# NixiTubeClock_IN-14.net
KiCad netlist of a schematic drawn in EAGLE
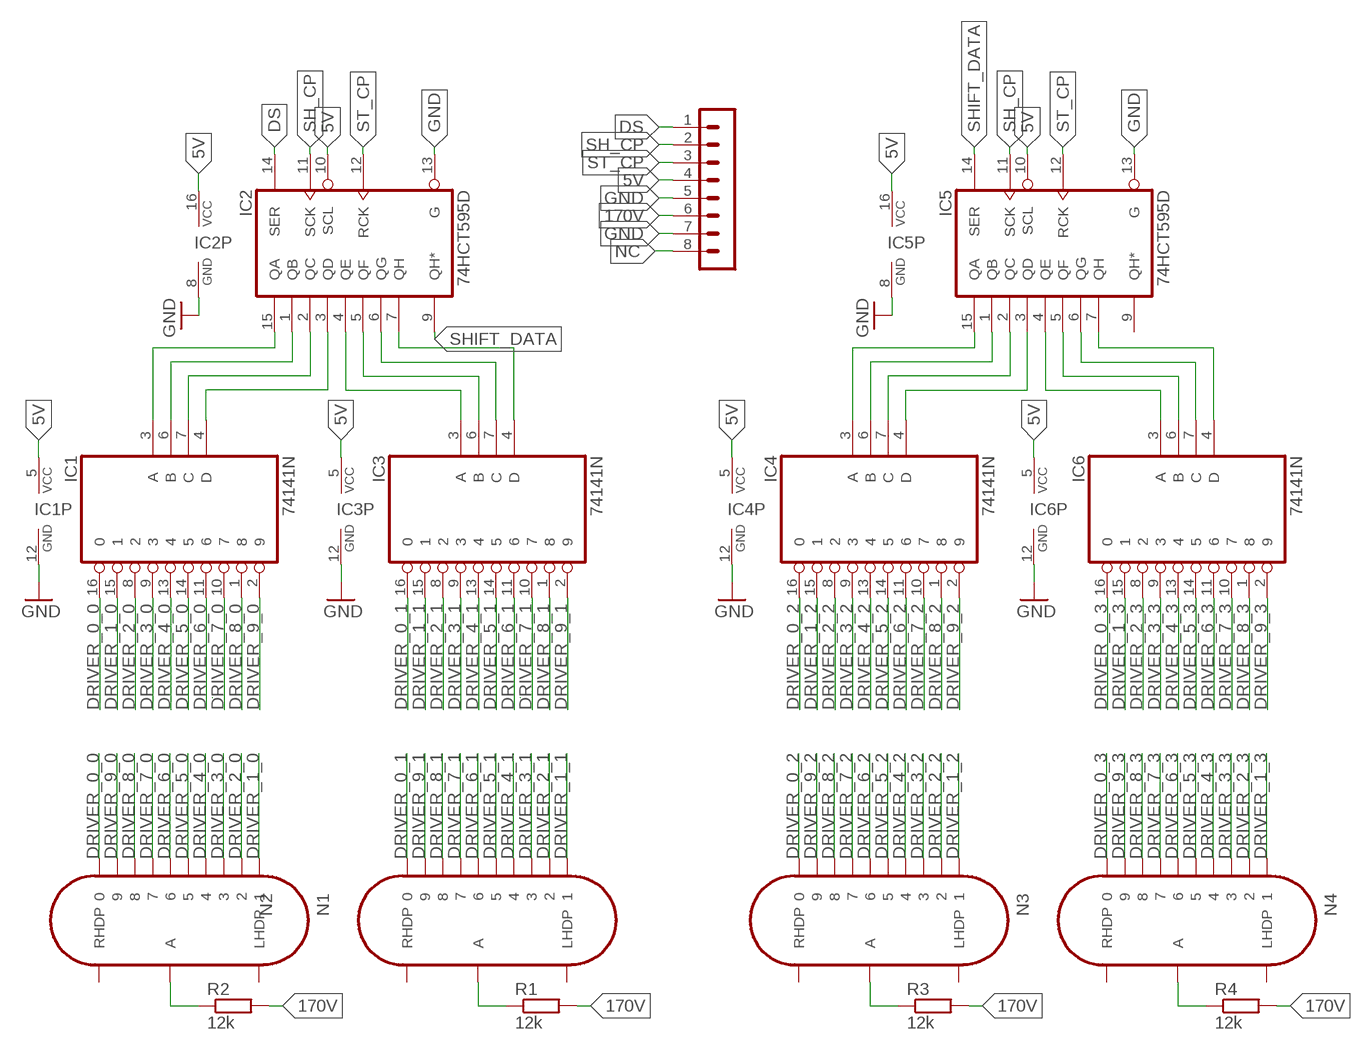
[diagram p0: schematic, sheet 1]

(export (version "E")
  (design (tool "Eeschema 10.0.6"))
  (components
    (comp (ref "IC1")
      (value "74141N")
      (footprint "eagle-import:DIL16")
      (libsource (lib "eagle-import") (part "74141N"))
    )
    (comp (ref "IC2")
      (value "74HCT595D")
      (footprint "eagle-import:SO16")
      (libsource (lib "eagle-import") (part "74595DHCT"))
    )
    (comp (ref "IC3")
      (value "74141N")
      (footprint "eagle-import:DIL16")
      (libsource (lib "eagle-import") (part "74141N"))
    )
    (comp (ref "IC4")
      (value "74141N")
      (footprint "eagle-import:DIL16")
      (libsource (lib "eagle-import") (part "74141N"))
    )
    (comp (ref "IC5")
      (value "74HCT595D")
      (footprint "eagle-import:SO16")
      (libsource (lib "eagle-import") (part "74595DHCT"))
    )
    (comp (ref "IC6")
      (value "74141N")
      (footprint "eagle-import:DIL16")
      (libsource (lib "eagle-import") (part "74141N"))
    )
    (comp (ref "N1")
      (value "IN-14")
      (footprint "eagle-import:IN-14")
      (libsource (lib "eagle-import") (part "IN-14"))
    )
    (comp (ref "N2")
      (value "IN-14")
      (footprint "eagle-import:IN-14")
      (libsource (lib "eagle-import") (part "IN-14"))
    )
    (comp (ref "N3")
      (value "IN-14")
      (footprint "eagle-import:IN-14")
      (libsource (lib "eagle-import") (part "IN-14"))
    )
    (comp (ref "N4")
      (value "IN-14")
      (footprint "eagle-import:IN-14")
      (libsource (lib "eagle-import") (part "IN-14"))
    )
    (comp (ref "R1")
      (value "12k")
      (footprint "eagle-import:R1206")
      (libsource (lib "eagle-import") (part "R-EU_1206R1206"))
    )
    (comp (ref "R2")
      (value "12k")
      (footprint "eagle-import:R1206")
      (libsource (lib "eagle-import") (part "R-EU_1206R1206"))
    )
    (comp (ref "R3")
      (value "12k")
      (footprint "eagle-import:R1206")
      (libsource (lib "eagle-import") (part "R-EU_1206R1206"))
    )
    (comp (ref "R4")
      (value "12k")
      (footprint "eagle-import:R1206")
      (libsource (lib "eagle-import") (part "R-EU_1206R1206"))
    )
    (comp (ref "SV2")
      (value "PINHEADER-1X8")
      (footprint "eagle-import:MA08-1")
      (libsource (lib "eagle-import") (part "PINHEADER-1X8"))
    )
  )
  (nets
    (net (code "1") (name "/DRIVER_0_0") (class "Default")
      (node (ref "IC1") (pin "16") (pinfunction "0_16") (pintype "open_collector"))
      (node (ref "N1") (pin "0") (pinfunction "0_0") (pintype "bidirectional"))
    )
    (net (code "2") (name "/DRIVER_0_1") (class "Default")
      (node (ref "IC3") (pin "16") (pinfunction "0_16") (pintype "open_collector"))
      (node (ref "N2") (pin "0") (pinfunction "0_0") (pintype "bidirectional"))
    )
    (net (code "3") (name "/DRIVER_0_2") (class "Default")
      (node (ref "IC4") (pin "16") (pinfunction "0_16") (pintype "open_collector"))
      (node (ref "N3") (pin "0") (pinfunction "0_0") (pintype "bidirectional"))
    )
    (net (code "4") (name "/DRIVER_0_3") (class "Default")
      (node (ref "IC6") (pin "16") (pinfunction "0_16") (pintype "open_collector"))
      (node (ref "N4") (pin "0") (pinfunction "0_0") (pintype "bidirectional"))
    )
    (net (code "5") (name "/DRIVER_1_0") (class "Default")
      (node (ref "IC1") (pin "15") (pinfunction "1_15") (pintype "open_collector"))
      (node (ref "N1") (pin "1") (pinfunction "1_1") (pintype "bidirectional"))
    )
    (net (code "6") (name "/DRIVER_1_1") (class "Default")
      (node (ref "IC3") (pin "15") (pinfunction "1_15") (pintype "open_collector"))
      (node (ref "N2") (pin "1") (pinfunction "1_1") (pintype "bidirectional"))
    )
    (net (code "7") (name "/DRIVER_1_2") (class "Default")
      (node (ref "IC4") (pin "15") (pinfunction "1_15") (pintype "open_collector"))
      (node (ref "N3") (pin "1") (pinfunction "1_1") (pintype "bidirectional"))
    )
    (net (code "8") (name "/DRIVER_1_3") (class "Default")
      (node (ref "IC6") (pin "15") (pinfunction "1_15") (pintype "open_collector"))
      (node (ref "N4") (pin "1") (pinfunction "1_1") (pintype "bidirectional"))
    )
    (net (code "9") (name "/DRIVER_2_0") (class "Default")
      (node (ref "IC1") (pin "8") (pinfunction "2_8") (pintype "open_collector"))
      (node (ref "N1") (pin "2") (pinfunction "2_2") (pintype "bidirectional"))
    )
    (net (code "10") (name "/DRIVER_2_1") (class "Default")
      (node (ref "IC3") (pin "8") (pinfunction "2_8") (pintype "open_collector"))
      (node (ref "N2") (pin "2") (pinfunction "2_2") (pintype "bidirectional"))
    )
    (net (code "11") (name "/DRIVER_2_2") (class "Default")
      (node (ref "IC4") (pin "8") (pinfunction "2_8") (pintype "open_collector"))
      (node (ref "N3") (pin "2") (pinfunction "2_2") (pintype "bidirectional"))
    )
    (net (code "12") (name "/DRIVER_2_3") (class "Default")
      (node (ref "IC6") (pin "8") (pinfunction "2_8") (pintype "open_collector"))
      (node (ref "N4") (pin "2") (pinfunction "2_2") (pintype "bidirectional"))
    )
    (net (code "13") (name "/DRIVER_3_0") (class "Default")
      (node (ref "IC1") (pin "9") (pinfunction "3_9") (pintype "open_collector"))
      (node (ref "N1") (pin "3") (pinfunction "3_3") (pintype "bidirectional"))
    )
    (net (code "14") (name "/DRIVER_3_1") (class "Default")
      (node (ref "IC3") (pin "9") (pinfunction "3_9") (pintype "open_collector"))
      (node (ref "N2") (pin "3") (pinfunction "3_3") (pintype "bidirectional"))
    )
    (net (code "15") (name "/DRIVER_3_2") (class "Default")
      (node (ref "IC4") (pin "9") (pinfunction "3_9") (pintype "open_collector"))
      (node (ref "N3") (pin "3") (pinfunction "3_3") (pintype "bidirectional"))
    )
    (net (code "16") (name "/DRIVER_3_3") (class "Default")
      (node (ref "IC6") (pin "9") (pinfunction "3_9") (pintype "open_collector"))
      (node (ref "N4") (pin "3") (pinfunction "3_3") (pintype "bidirectional"))
    )
    (net (code "17") (name "/DRIVER_4_0") (class "Default")
      (node (ref "IC1") (pin "13") (pinfunction "4_13") (pintype "open_collector"))
      (node (ref "N1") (pin "4") (pinfunction "4_4") (pintype "bidirectional"))
    )
    (net (code "18") (name "/DRIVER_4_1") (class "Default")
      (node (ref "IC3") (pin "13") (pinfunction "4_13") (pintype "open_collector"))
      (node (ref "N2") (pin "4") (pinfunction "4_4") (pintype "bidirectional"))
    )
    (net (code "19") (name "/DRIVER_4_2") (class "Default")
      (node (ref "IC4") (pin "13") (pinfunction "4_13") (pintype "open_collector"))
      (node (ref "N3") (pin "4") (pinfunction "4_4") (pintype "bidirectional"))
    )
    (net (code "20") (name "/DRIVER_4_3") (class "Default")
      (node (ref "IC6") (pin "13") (pinfunction "4_13") (pintype "open_collector"))
      (node (ref "N4") (pin "4") (pinfunction "4_4") (pintype "bidirectional"))
    )
    (net (code "21") (name "/DRIVER_5_0") (class "Default")
      (node (ref "IC1") (pin "14") (pinfunction "5_14") (pintype "open_collector"))
      (node (ref "N1") (pin "5") (pinfunction "5_5") (pintype "bidirectional"))
    )
    (net (code "22") (name "/DRIVER_5_1") (class "Default")
      (node (ref "IC3") (pin "14") (pinfunction "5_14") (pintype "open_collector"))
      (node (ref "N2") (pin "5") (pinfunction "5_5") (pintype "bidirectional"))
    )
    (net (code "23") (name "/DRIVER_5_2") (class "Default")
      (node (ref "IC4") (pin "14") (pinfunction "5_14") (pintype "open_collector"))
      (node (ref "N3") (pin "5") (pinfunction "5_5") (pintype "bidirectional"))
    )
    (net (code "24") (name "/DRIVER_5_3") (class "Default")
      (node (ref "IC6") (pin "14") (pinfunction "5_14") (pintype "open_collector"))
      (node (ref "N4") (pin "5") (pinfunction "5_5") (pintype "bidirectional"))
    )
    (net (code "25") (name "/DRIVER_6_0") (class "Default")
      (node (ref "IC1") (pin "11") (pinfunction "6_11") (pintype "open_collector"))
      (node (ref "N1") (pin "6") (pinfunction "6_6") (pintype "bidirectional"))
    )
    (net (code "26") (name "/DRIVER_6_1") (class "Default")
      (node (ref "IC3") (pin "11") (pinfunction "6_11") (pintype "open_collector"))
      (node (ref "N2") (pin "6") (pinfunction "6_6") (pintype "bidirectional"))
    )
    (net (code "27") (name "/DRIVER_6_2") (class "Default")
      (node (ref "IC4") (pin "11") (pinfunction "6_11") (pintype "open_collector"))
      (node (ref "N3") (pin "6") (pinfunction "6_6") (pintype "bidirectional"))
    )
    (net (code "28") (name "/DRIVER_6_3") (class "Default")
      (node (ref "IC6") (pin "11") (pinfunction "6_11") (pintype "open_collector"))
      (node (ref "N4") (pin "6") (pinfunction "6_6") (pintype "bidirectional"))
    )
    (net (code "29") (name "/DRIVER_7_0") (class "Default")
      (node (ref "IC1") (pin "10") (pinfunction "7_10") (pintype "open_collector"))
      (node (ref "N1") (pin "7") (pinfunction "7_7") (pintype "bidirectional"))
    )
    (net (code "30") (name "/DRIVER_7_1") (class "Default")
      (node (ref "IC3") (pin "10") (pinfunction "7_10") (pintype "open_collector"))
      (node (ref "N2") (pin "7") (pinfunction "7_7") (pintype "bidirectional"))
    )
    (net (code "31") (name "/DRIVER_7_2") (class "Default")
      (node (ref "IC4") (pin "10") (pinfunction "7_10") (pintype "open_collector"))
      (node (ref "N3") (pin "7") (pinfunction "7_7") (pintype "bidirectional"))
    )
    (net (code "32") (name "/DRIVER_7_3") (class "Default")
      (node (ref "IC6") (pin "10") (pinfunction "7_10") (pintype "open_collector"))
      (node (ref "N4") (pin "7") (pinfunction "7_7") (pintype "bidirectional"))
    )
    (net (code "33") (name "/DRIVER_8_0") (class "Default")
      (node (ref "IC1") (pin "1") (pinfunction "8_1") (pintype "open_collector"))
      (node (ref "N1") (pin "8") (pinfunction "8_8") (pintype "bidirectional"))
    )
    (net (code "34") (name "/DRIVER_8_1") (class "Default")
      (node (ref "IC3") (pin "1") (pinfunction "8_1") (pintype "open_collector"))
      (node (ref "N2") (pin "8") (pinfunction "8_8") (pintype "bidirectional"))
    )
    (net (code "35") (name "/DRIVER_8_2") (class "Default")
      (node (ref "IC4") (pin "1") (pinfunction "8_1") (pintype "open_collector"))
      (node (ref "N3") (pin "8") (pinfunction "8_8") (pintype "bidirectional"))
    )
    (net (code "36") (name "/DRIVER_8_3") (class "Default")
      (node (ref "IC6") (pin "1") (pinfunction "8_1") (pintype "open_collector"))
      (node (ref "N4") (pin "8") (pinfunction "8_8") (pintype "bidirectional"))
    )
    (net (code "37") (name "/DRIVER_9_0") (class "Default")
      (node (ref "IC1") (pin "2") (pinfunction "9_2") (pintype "open_collector"))
      (node (ref "N1") (pin "9") (pinfunction "9_9") (pintype "bidirectional"))
    )
    (net (code "38") (name "/DRIVER_9_1") (class "Default")
      (node (ref "IC3") (pin "2") (pinfunction "9_2") (pintype "open_collector"))
      (node (ref "N2") (pin "9") (pinfunction "9_9") (pintype "bidirectional"))
    )
    (net (code "39") (name "/DRIVER_9_2") (class "Default")
      (node (ref "IC4") (pin "2") (pinfunction "9_2") (pintype "open_collector"))
      (node (ref "N3") (pin "9") (pinfunction "9_9") (pintype "bidirectional"))
    )
    (net (code "40") (name "/DRIVER_9_3") (class "Default")
      (node (ref "IC6") (pin "2") (pinfunction "9_2") (pintype "open_collector"))
      (node (ref "N4") (pin "9") (pinfunction "9_9") (pintype "bidirectional"))
    )
    (net (code "41") (name "5V") (class "Default")
      (node (ref "IC1") (pin "5") (pinfunction "VCC_5") (pintype "power_in"))
      (node (ref "IC2") (pin "10") (pinfunction "SCL_10") (pintype "input"))
      (node (ref "IC2") (pin "16") (pinfunction "VCC_16") (pintype "power_in"))
      (node (ref "IC3") (pin "5") (pinfunction "VCC_5") (pintype "power_in"))
      (node (ref "IC4") (pin "5") (pinfunction "VCC_5") (pintype "power_in"))
      (node (ref "IC5") (pin "10") (pinfunction "SCL_10") (pintype "input"))
      (node (ref "IC5") (pin "16") (pinfunction "VCC_16") (pintype "power_in"))
      (node (ref "IC6") (pin "5") (pinfunction "VCC_5") (pintype "power_in"))
      (node (ref "SV2") (pin "4") (pinfunction "4_4") (pintype "passive"))
    )
    (net (code "42") (name "170V") (class "Default")
      (node (ref "R1") (pin "2") (pinfunction "2_2") (pintype "passive"))
      (node (ref "R2") (pin "2") (pinfunction "2_2") (pintype "passive"))
      (node (ref "R3") (pin "2") (pinfunction "2_2") (pintype "passive"))
      (node (ref "R4") (pin "2") (pinfunction "2_2") (pintype "passive"))
      (node (ref "SV2") (pin "6") (pinfunction "6_6") (pintype "passive"))
    )
    (net (code "43") (name "DS") (class "Default")
      (node (ref "IC2") (pin "14") (pinfunction "SER_14") (pintype "input"))
      (node (ref "SV2") (pin "1") (pinfunction "1_1") (pintype "passive"))
    )
    (net (code "44") (name "GND") (class "Default")
      (node (ref "IC1") (pin "12") (pinfunction "GND_12") (pintype "power_in"))
      (node (ref "IC2") (pin "13") (pinfunction "G_13") (pintype "input"))
      (node (ref "IC2") (pin "8") (pinfunction "GND_8") (pintype "power_in"))
      (node (ref "IC3") (pin "12") (pinfunction "GND_12") (pintype "power_in"))
      (node (ref "IC4") (pin "12") (pinfunction "GND_12") (pintype "power_in"))
      (node (ref "IC5") (pin "13") (pinfunction "G_13") (pintype "input"))
      (node (ref "IC5") (pin "8") (pinfunction "GND_8") (pintype "power_in"))
      (node (ref "IC6") (pin "12") (pinfunction "GND_12") (pintype "power_in"))
      (node (ref "SV2") (pin "5") (pinfunction "5_5") (pintype "passive"))
      (node (ref "SV2") (pin "7") (pinfunction "7_7") (pintype "passive"))
    )
    (net (code "45") (name "NC") (class "Default")
      (node (ref "SV2") (pin "8") (pinfunction "8_8") (pintype "passive"))
    )
    (net (code "46") (name "Net-(IC1A-A)") (class "Default")
      (node (ref "IC1") (pin "3") (pinfunction "A_3") (pintype "input"))
      (node (ref "IC2") (pin "15") (pinfunction "QA_15") (pintype "tri_state"))
    )
    (net (code "47") (name "Net-(IC1A-B)") (class "Default")
      (node (ref "IC1") (pin "6") (pinfunction "B_6") (pintype "input"))
      (node (ref "IC2") (pin "1") (pinfunction "QB_1") (pintype "tri_state"))
    )
    (net (code "48") (name "Net-(IC1A-C)") (class "Default")
      (node (ref "IC1") (pin "7") (pinfunction "C_7") (pintype "input"))
      (node (ref "IC2") (pin "2") (pinfunction "QC_2") (pintype "tri_state"))
    )
    (net (code "49") (name "Net-(IC1A-D)") (class "Default")
      (node (ref "IC1") (pin "4") (pinfunction "D_4") (pintype "input"))
      (node (ref "IC2") (pin "3") (pinfunction "QD_3") (pintype "tri_state"))
    )
    (net (code "50") (name "Net-(IC2A-QE)") (class "Default")
      (node (ref "IC2") (pin "4") (pinfunction "QE_4") (pintype "tri_state"))
      (node (ref "IC3") (pin "3") (pinfunction "A_3") (pintype "input"))
    )
    (net (code "51") (name "Net-(IC2A-QF)") (class "Default")
      (node (ref "IC2") (pin "5") (pinfunction "QF_5") (pintype "tri_state"))
      (node (ref "IC3") (pin "6") (pinfunction "B_6") (pintype "input"))
    )
    (net (code "52") (name "Net-(IC2A-QG)") (class "Default")
      (node (ref "IC2") (pin "6") (pinfunction "QG_6") (pintype "tri_state"))
      (node (ref "IC3") (pin "7") (pinfunction "C_7") (pintype "input"))
    )
    (net (code "53") (name "Net-(IC2A-QH)") (class "Default")
      (node (ref "IC2") (pin "7") (pinfunction "QH_7") (pintype "tri_state"))
      (node (ref "IC3") (pin "4") (pinfunction "D_4") (pintype "input"))
    )
    (net (code "54") (name "Net-(IC4A-A)") (class "Default")
      (node (ref "IC4") (pin "3") (pinfunction "A_3") (pintype "input"))
      (node (ref "IC5") (pin "15") (pinfunction "QA_15") (pintype "tri_state"))
    )
    (net (code "55") (name "Net-(IC4A-B)") (class "Default")
      (node (ref "IC4") (pin "6") (pinfunction "B_6") (pintype "input"))
      (node (ref "IC5") (pin "1") (pinfunction "QB_1") (pintype "tri_state"))
    )
    (net (code "56") (name "Net-(IC4A-C)") (class "Default")
      (node (ref "IC4") (pin "7") (pinfunction "C_7") (pintype "input"))
      (node (ref "IC5") (pin "2") (pinfunction "QC_2") (pintype "tri_state"))
    )
    (net (code "57") (name "Net-(IC4A-D)") (class "Default")
      (node (ref "IC4") (pin "4") (pinfunction "D_4") (pintype "input"))
      (node (ref "IC5") (pin "3") (pinfunction "QD_3") (pintype "tri_state"))
    )
    (net (code "58") (name "Net-(IC5A-QE)") (class "Default")
      (node (ref "IC5") (pin "4") (pinfunction "QE_4") (pintype "tri_state"))
      (node (ref "IC6") (pin "3") (pinfunction "A_3") (pintype "input"))
    )
    (net (code "59") (name "Net-(IC5A-QF)") (class "Default")
      (node (ref "IC5") (pin "5") (pinfunction "QF_5") (pintype "tri_state"))
      (node (ref "IC6") (pin "6") (pinfunction "B_6") (pintype "input"))
    )
    (net (code "60") (name "Net-(IC5A-QG)") (class "Default")
      (node (ref "IC5") (pin "6") (pinfunction "QG_6") (pintype "tri_state"))
      (node (ref "IC6") (pin "7") (pinfunction "C_7") (pintype "input"))
    )
    (net (code "61") (name "Net-(IC5A-QH)") (class "Default")
      (node (ref "IC5") (pin "7") (pinfunction "QH_7") (pintype "tri_state"))
      (node (ref "IC6") (pin "4") (pinfunction "D_4") (pintype "input"))
    )
    (net (code "62") (name "Net-(N1-PadA)") (class "Default")
      (node (ref "N1") (pin "A") (pinfunction "A_A") (pintype "bidirectional"))
      (node (ref "R2") (pin "1") (pinfunction "1_1") (pintype "passive"))
    )
    (net (code "63") (name "Net-(N2-PadA)") (class "Default")
      (node (ref "N2") (pin "A") (pinfunction "A_A") (pintype "bidirectional"))
      (node (ref "R1") (pin "1") (pinfunction "1_1") (pintype "passive"))
    )
    (net (code "64") (name "Net-(N3-PadA)") (class "Default")
      (node (ref "N3") (pin "A") (pinfunction "A_A") (pintype "bidirectional"))
      (node (ref "R3") (pin "1") (pinfunction "1_1") (pintype "passive"))
    )
    (net (code "65") (name "Net-(N4-PadA)") (class "Default")
      (node (ref "N4") (pin "A") (pinfunction "A_A") (pintype "bidirectional"))
      (node (ref "R4") (pin "1") (pinfunction "1_1") (pintype "passive"))
    )
    (net (code "66") (name "SHIFT_DATA") (class "Default")
      (node (ref "IC2") (pin "9") (pinfunction "QH*_9") (pintype "tri_state"))
      (node (ref "IC5") (pin "14") (pinfunction "SER_14") (pintype "input"))
    )
    (net (code "67") (name "SH_CP") (class "Default")
      (node (ref "IC2") (pin "11") (pinfunction "SCK_11") (pintype "input"))
      (node (ref "IC5") (pin "11") (pinfunction "SCK_11") (pintype "input"))
      (node (ref "SV2") (pin "2") (pinfunction "2_2") (pintype "passive"))
    )
    (net (code "68") (name "ST_CP") (class "Default")
      (node (ref "IC2") (pin "12") (pinfunction "RCK_12") (pintype "input"))
      (node (ref "IC5") (pin "12") (pinfunction "RCK_12") (pintype "input"))
      (node (ref "SV2") (pin "3") (pinfunction "3_3") (pintype "passive"))
    )
    (net (code "69") (name "unconnected-(IC5A-QH*-Pad9)") (class "Default")
      (node (ref "IC5") (pin "9") (pinfunction "QH*_9") (pintype "tri_state"))
    )
    (net (code "70") (name "unconnected-(N1-PadLHDP)") (class "Default")
      (node (ref "N1") (pin "LHDP") (pinfunction "LHDP_LHDP") (pintype "bidirectional"))
    )
    (net (code "71") (name "unconnected-(N1-PadRHDP)") (class "Default")
      (node (ref "N1") (pin "RHDP") (pinfunction "RHDP_RHDP") (pintype "bidirectional"))
    )
    (net (code "72") (name "unconnected-(N2-PadLHDP)") (class "Default")
      (node (ref "N2") (pin "LHDP") (pinfunction "LHDP_LHDP") (pintype "bidirectional"))
    )
    (net (code "73") (name "unconnected-(N2-PadRHDP)") (class "Default")
      (node (ref "N2") (pin "RHDP") (pinfunction "RHDP_RHDP") (pintype "bidirectional"))
    )
    (net (code "74") (name "unconnected-(N3-PadLHDP)") (class "Default")
      (node (ref "N3") (pin "LHDP") (pinfunction "LHDP_LHDP") (pintype "bidirectional"))
    )
    (net (code "75") (name "unconnected-(N3-PadRHDP)") (class "Default")
      (node (ref "N3") (pin "RHDP") (pinfunction "RHDP_RHDP") (pintype "bidirectional"))
    )
    (net (code "76") (name "unconnected-(N4-PadLHDP)") (class "Default")
      (node (ref "N4") (pin "LHDP") (pinfunction "LHDP_LHDP") (pintype "bidirectional"))
    )
    (net (code "77") (name "unconnected-(N4-PadRHDP)") (class "Default")
      (node (ref "N4") (pin "RHDP") (pinfunction "RHDP_RHDP") (pintype "bidirectional"))
    )
  )
)
